# CAN_System.net
KiCad netlist of a schematic drawn in Altium Designer
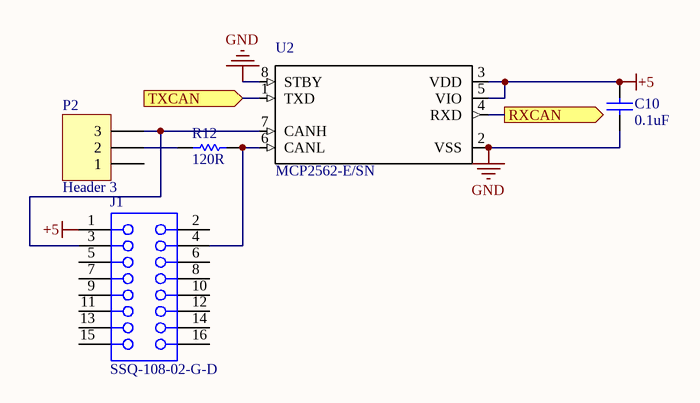
[diagram p0: CAN System.SchDoc]

(export (version "E")
  (design (tool "Eeschema 10.0.6"))
  (components
    (comp (ref "C10")
      (value "0.1uF")
      (footprint "CAPC2013X94X50LL20T25")
      (description "Chip Capacitor, 0.1 uF, +/- 5%, 50 V, -55 to 125 degC, 0805 (2012 Metric), RoHS, Tape and Reel")
      (fields (field (name "TOLERANCE") "5%") (field (name "MANUFACTURER") "AVX"))
      (libsource (lib "Altium Content Vault") (part "CAP-NP-2"))
    )
    (comp (ref "J1")
      (value "SSQ-108-02-G-D")
      (footprint "SMTC-SSQ-108-02-X-D")
      (description "SQ Post Socket, Through-hole, Vertical, -55 to 125 degC, 2.54 mm Pitch, 16-Pin, Female, RoHS")
      (fields (field (name "MANUFACTURER") "Samtec"))
      (libsource (lib "Husky Robotics Standard Library 2019-2020") (part "CMP-1023-00300-1"))
    )
    (comp (ref "P2")
      (value "Header 3")
      (footprint "HDR1X3")
      (description "Header, 3-Pin")
      (fields (field (name "PUBLISHER") "Altium Limited"))
      (libsource (lib "Miscellaneous Connectors") (part "Header 3"))
    )
    (comp (ref "R12")
      (value "120R")
      (footprint "RESC0805(2012)_N")
      (description "120R 0.125W 5% 0805 (2012 Metric)  SMD")
      (fields (field (name "TOLERANCE") "5 %") (field (name "POWER") "0.125 W"))
      (libsource (lib "Husky Robotics Standard Library 2019-2020") (part "120R 5% 0805"))
    )
    (comp (ref "U2")
      (value "MCP2562-E/SN")
      (footprint "SOIC127P600X175-8N")
      (description "Microchip MCP2562-E/SN, CAN Transceiver 1MBps 1-channel IEC 61000-4-2, 8-Pin SOIC")
      (fields (field (name "MF") "Microchip"))
      (libsource (lib "Husky Robotics Standard Library 2019-2020") (part "MCP2562-E/SN"))
    )
  )
  (nets
    (net (code "1") (name "+5") (class "Default")
      (node (ref "C10") (pin "2") (pinfunction "2_2") (pintype "passive"))
      (node (ref "J1") (pin "1") (pinfunction "1_1") (pintype "passive"))
      (node (ref "U2") (pin "3") (pinfunction "VDD_3") (pintype "power_in"))
      (node (ref "U2") (pin "5") (pinfunction "VIO_5") (pintype "power_in"))
    )
    (net (code "2") (name "/RXCAN") (class "Default")
      (node (ref "U2") (pin "4") (pinfunction "RXD_4") (pintype "output"))
    )
    (net (code "3") (name "/TXCAN") (class "Default")
      (node (ref "U2") (pin "1") (pinfunction "TXD_1") (pintype "input"))
    )
    (net (code "4") (name "GND") (class "Default")
      (node (ref "C10") (pin "1") (pinfunction "1_1") (pintype "passive"))
      (node (ref "U2") (pin "2") (pinfunction "VSS_2") (pintype "power_in"))
      (node (ref "U2") (pin "8") (pinfunction "STBY_8") (pintype "input"))
    )
    (net (code "5") (name "Net-(P2-Pad2)") (class "Default")
      (node (ref "P2") (pin "2") (pinfunction "2_2") (pintype "passive"))
      (node (ref "R12") (pin "1") (pinfunction "1_1") (pintype "passive"))
    )
    (net (code "6") (name "Net-(U2-CANH)") (class "Default")
      (node (ref "J1") (pin "3") (pinfunction "3_3") (pintype "passive"))
      (node (ref "P2") (pin "3") (pinfunction "3_3") (pintype "passive"))
      (node (ref "U2") (pin "7") (pinfunction "CANH_7") (pintype "input"))
    )
    (net (code "7") (name "Net-(U2-CANL)") (class "Default")
      (node (ref "J1") (pin "4") (pinfunction "4_4") (pintype "passive"))
      (node (ref "R12") (pin "2") (pinfunction "2_2") (pintype "passive"))
      (node (ref "U2") (pin "6") (pinfunction "CANL_6") (pintype "input"))
    )
    (net (code "8") (name "unconnected-(J1-Pad2)") (class "Default")
      (node (ref "J1") (pin "2") (pinfunction "2_2") (pintype "passive"))
    )
    (net (code "9") (name "unconnected-(J1-Pad5)") (class "Default")
      (node (ref "J1") (pin "5") (pinfunction "5_5") (pintype "passive"))
    )
    (net (code "10") (name "unconnected-(J1-Pad6)") (class "Default")
      (node (ref "J1") (pin "6") (pinfunction "6_6") (pintype "passive"))
    )
    (net (code "11") (name "unconnected-(J1-Pad7)") (class "Default")
      (node (ref "J1") (pin "7") (pinfunction "7_7") (pintype "passive"))
    )
    (net (code "12") (name "unconnected-(J1-Pad8)") (class "Default")
      (node (ref "J1") (pin "8") (pinfunction "8_8") (pintype "passive"))
    )
    (net (code "13") (name "unconnected-(J1-Pad9)") (class "Default")
      (node (ref "J1") (pin "9") (pinfunction "9_9") (pintype "passive"))
    )
    (net (code "14") (name "unconnected-(J1-Pad10)") (class "Default")
      (node (ref "J1") (pin "10") (pinfunction "10_10") (pintype "passive"))
    )
    (net (code "15") (name "unconnected-(J1-Pad11)") (class "Default")
      (node (ref "J1") (pin "11") (pinfunction "11_11") (pintype "passive"))
    )
    (net (code "16") (name "unconnected-(J1-Pad12)") (class "Default")
      (node (ref "J1") (pin "12") (pinfunction "12_12") (pintype "passive"))
    )
    (net (code "17") (name "unconnected-(J1-Pad13)") (class "Default")
      (node (ref "J1") (pin "13") (pinfunction "13_13") (pintype "passive"))
    )
    (net (code "18") (name "unconnected-(J1-Pad14)") (class "Default")
      (node (ref "J1") (pin "14") (pinfunction "14_14") (pintype "passive"))
    )
    (net (code "19") (name "unconnected-(J1-Pad15)") (class "Default")
      (node (ref "J1") (pin "15") (pinfunction "15_15") (pintype "passive"))
    )
    (net (code "20") (name "unconnected-(J1-Pad16)") (class "Default")
      (node (ref "J1") (pin "16") (pinfunction "16_16") (pintype "passive"))
    )
    (net (code "21") (name "unconnected-(P2-Pad1)") (class "Default")
      (node (ref "P2") (pin "1") (pinfunction "1_1") (pintype "passive"))
    )
  )
)
